# STM32WB55.net
KiCad netlist of a schematic drawn in Altium Designer
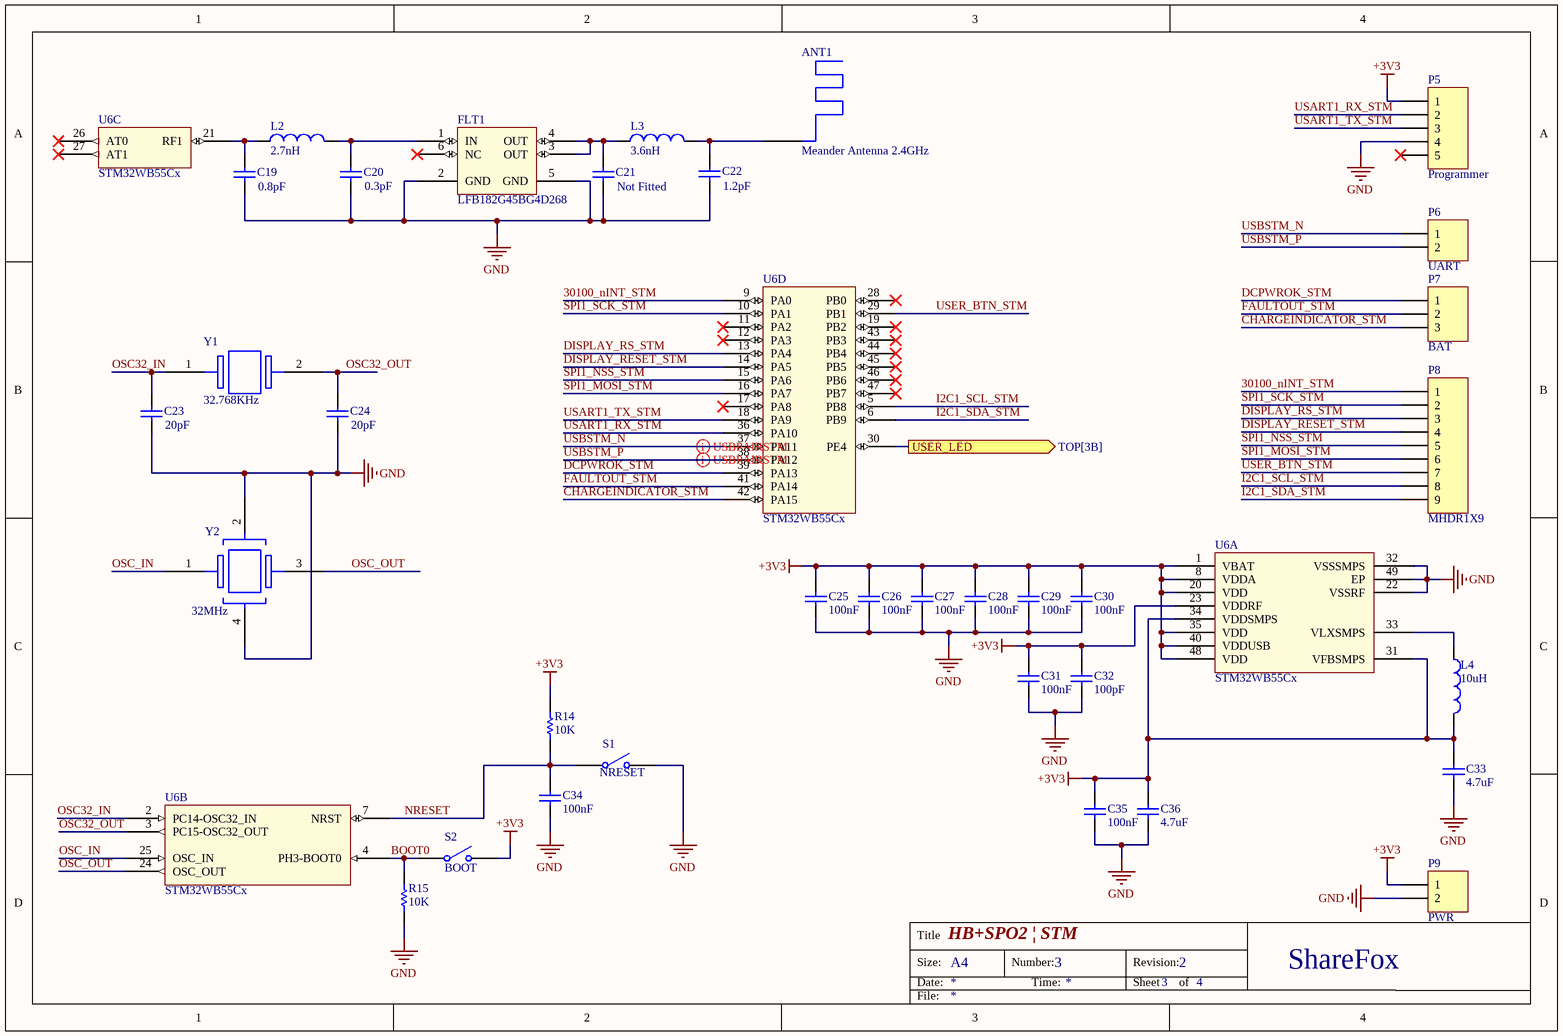
[diagram p0: STM32WB55.SchDoc]

(export (version "E")
  (design (tool "Eeschema 10.0.6"))
  (components
    (comp (ref "ANT1")
      (value "Meander Antenna 2.4GHz")
      (footprint "Meander2.4G")
      (description "PCB TRACE\r\nDONT TRY TO LOOK FOR PARTS")
      (libsource (lib "GenericContinued") (part "Meander Antenna 2.4GHz"))
    )
    (comp (ref "C19")
      (value "0.8pF")
      (footprint "C_0603")
      (description "Capacitor")
      (fields (field (name "PUBLISHER") "Altium Limited"))
      (libsource (lib "Miscellaneous Devices") (part "Cap"))
    )
    (comp (ref "C20")
      (value "0.3pF")
      (footprint "C_0603")
      (description "Capacitor")
      (fields (field (name "PUBLISHER") "Altium Limited"))
      (libsource (lib "Miscellaneous Devices") (part "Cap"))
    )
    (comp (ref "C21")
      (value "Not Fitted")
      (footprint "C_0603")
      (description "Capacitor")
      (fields (field (name "PUBLISHER") "Altium Limited"))
      (libsource (lib "Miscellaneous Devices") (part "Cap"))
    )
    (comp (ref "C22")
      (value "1.2pF")
      (footprint "C_0603")
      (description "Capacitor")
      (fields (field (name "PUBLISHER") "Altium Limited"))
      (libsource (lib "Miscellaneous Devices") (part "Cap"))
    )
    (comp (ref "C23")
      (value "20pF")
      (footprint "C_0603")
      (description "Capacitor")
      (fields (field (name "PUBLISHER") "Altium Limited"))
      (libsource (lib "Miscellaneous Devices") (part "Cap"))
    )
    (comp (ref "C24")
      (value "20pF")
      (footprint "C_0603")
      (description "Capacitor")
      (fields (field (name "PUBLISHER") "Altium Limited"))
      (libsource (lib "Miscellaneous Devices") (part "Cap"))
    )
    (comp (ref "C25")
      (value "100nF")
      (footprint "C_0603")
      (description "Capacitor")
      (fields (field (name "PUBLISHER") "Altium Limited"))
      (libsource (lib "Miscellaneous Devices") (part "Cap"))
    )
    (comp (ref "C26")
      (value "100nF")
      (footprint "C_0603")
      (description "Capacitor")
      (fields (field (name "PUBLISHER") "Altium Limited"))
      (libsource (lib "Miscellaneous Devices") (part "Cap"))
    )
    (comp (ref "C27")
      (value "100nF")
      (footprint "C_0603")
      (description "Capacitor")
      (fields (field (name "PUBLISHER") "Altium Limited"))
      (libsource (lib "Miscellaneous Devices") (part "Cap"))
    )
    (comp (ref "C28")
      (value "100nF")
      (footprint "C_0603")
      (description "Capacitor")
      (fields (field (name "PUBLISHER") "Altium Limited"))
      (libsource (lib "Miscellaneous Devices") (part "Cap"))
    )
    (comp (ref "C29")
      (value "100nF")
      (footprint "C_0603")
      (description "Capacitor")
      (fields (field (name "PUBLISHER") "Altium Limited"))
      (libsource (lib "Miscellaneous Devices") (part "Cap"))
    )
    (comp (ref "C30")
      (value "100nF")
      (footprint "C_0603")
      (description "Capacitor")
      (fields (field (name "PUBLISHER") "Altium Limited"))
      (libsource (lib "Miscellaneous Devices") (part "Cap"))
    )
    (comp (ref "C31")
      (value "100nF")
      (footprint "C_0603")
      (description "Capacitor")
      (fields (field (name "PUBLISHER") "Altium Limited"))
      (libsource (lib "Miscellaneous Devices") (part "Cap"))
    )
    (comp (ref "C32")
      (value "100pF")
      (footprint "C_0603")
      (description "Capacitor")
      (fields (field (name "PUBLISHER") "Altium Limited"))
      (libsource (lib "Miscellaneous Devices") (part "Cap"))
    )
    (comp (ref "C33")
      (value "4.7uF")
      (footprint "C_1206")
      (description "Capacitor")
      (fields (field (name "PUBLISHER") "Altium Limited"))
      (libsource (lib "Miscellaneous Devices") (part "Cap"))
    )
    (comp (ref "C34")
      (value "100nF")
      (footprint "C_0603")
      (description "Capacitor")
      (fields (field (name "PUBLISHER") "Altium Limited"))
      (libsource (lib "Miscellaneous Devices") (part "Cap"))
    )
    (comp (ref "C35")
      (value "100nF")
      (footprint "C_0603")
      (description "Capacitor")
      (fields (field (name "PUBLISHER") "Altium Limited"))
      (libsource (lib "Miscellaneous Devices") (part "Cap"))
    )
    (comp (ref "C36")
      (value "4.7uF")
      (footprint "C_1206")
      (description "Capacitor")
      (fields (field (name "PUBLISHER") "Altium Limited"))
      (libsource (lib "Miscellaneous Devices") (part "Cap"))
    )
    (comp (ref "FLT1")
      (value "LFB182G45BG4D268")
      (footprint "LFB182G45BG4D268")
      (description "Ultra-small, low-profiled, lightweight band-pass filters.")
      (libsource (lib "GenericContinued") (part "LFB182G45BG4D268"))
    )
    (comp (ref "L2")
      (value "2.7nH")
      (footprint "L-0603")
      (description "Inductor")
      (fields (field (name "PUBLISHER") "Altium Limited"))
      (libsource (lib "Miscellaneous Devices") (part "Inductor"))
    )
    (comp (ref "L3")
      (value "3.6nH")
      (footprint "L-0603")
      (description "Inductor")
      (fields (field (name "PUBLISHER") "Altium Limited"))
      (libsource (lib "Miscellaneous Devices") (part "Inductor"))
    )
    (comp (ref "L4")
      (value "10uH")
      (footprint "L-0603")
      (description "Inductor")
      (fields (field (name "PUBLISHER") "Altium Limited"))
      (libsource (lib "Miscellaneous Devices") (part "Inductor"))
    )
    (comp (ref "P5")
      (value "Programmer")
      (footprint "HDR1X5")
      (description "Header, 5-Pin")
      (fields (field (name "PUBLISHER") "Altium Limited"))
      (libsource (lib "Miscellaneous Connectors") (part "MHDR1X5"))
    )
    (comp (ref "P6")
      (value "UART")
      (footprint "MHDR1X2")
      (description "Header, 2-Pin")
      (fields (field (name "PUBLISHER") "Altium Limited"))
      (libsource (lib "Miscellaneous Connectors") (part "MHDR1X2"))
    )
    (comp (ref "P7")
      (value "BAT")
      (footprint "MHDR1X3")
      (description "Header, 3-Pin")
      (fields (field (name "PUBLISHER") "Altium Limited"))
      (libsource (lib "Miscellaneous Connectors") (part "MHDR1X3"))
    )
    (comp (ref "P8")
      (value "MHDR1X9")
      (footprint "MHDR1X9")
      (description "Header, 9-Pin")
      (fields (field (name "PUBLISHER") "Altium Limited"))
      (libsource (lib "Miscellaneous Connectors") (part "MHDR1X9"))
    )
    (comp (ref "P9")
      (value "PWR")
      (footprint "MHDR1X2")
      (description "Header, 2-Pin")
      (fields (field (name "PUBLISHER") "Altium Limited"))
      (libsource (lib "Miscellaneous Connectors") (part "MHDR1X2"))
    )
    (comp (ref "R14")
      (value "10K")
      (footprint "C_0603")
      (description "Resistor")
      (fields (field (name "PUBLISHER") "Altium Limited"))
      (libsource (lib "Miscellaneous Devices") (part "Res1"))
    )
    (comp (ref "R15")
      (value "10K")
      (footprint "C_0603")
      (description "Resistor")
      (fields (field (name "PUBLISHER") "Altium Limited"))
      (libsource (lib "Miscellaneous Devices") (part "Res1"))
    )
    (comp (ref "S1")
      (value "NRESET")
      (footprint "B3U-1000P-B")
      (description "Single-Pole, Single-Throw Switch")
      (fields (field (name "PUBLISHER") "Altium Limited"))
      (libsource (lib "Miscellaneous Devices") (part "SW-SPST"))
    )
    (comp (ref "S2")
      (value "BOOT")
      (footprint "B3U-1000P-B")
      (description "Single-Pole, Single-Throw Switch")
      (fields (field (name "PUBLISHER") "Altium Limited"))
      (libsource (lib "Miscellaneous Devices") (part "SW-SPST"))
    )
    (comp (ref "U6")
      (value "STM32WB55Cx")
      (footprint "QFN48P50S700x700EP560x560")
      (libsource (lib "ST") (part "STM32WB55Cx"))
    )
    (comp (ref "Y1")
      (value "32.768KHz")
      (footprint "ECX-31B")
      (libsource (lib "GenericContinued") (part "XTAL 3215"))
    )
    (comp (ref "Y2")
      (value "32MHz")
      (footprint "Y_3225")
      (libsource (lib "GenericContinued") (part "XTAL 3225 2_4GND"))
    )
  )
  (nets
    (net (code "1") (name "+3V3") (class "Default")
      (node (ref "C25") (pin "2") (pinfunction "2_2") (pintype "passive"))
      (node (ref "C26") (pin "2") (pinfunction "2_2") (pintype "passive"))
      (node (ref "C27") (pin "2") (pinfunction "2_2") (pintype "passive"))
      (node (ref "C28") (pin "2") (pinfunction "2_2") (pintype "passive"))
      (node (ref "C29") (pin "2") (pinfunction "2_2") (pintype "passive"))
      (node (ref "C30") (pin "2") (pinfunction "2_2") (pintype "passive"))
      (node (ref "C31") (pin "2") (pinfunction "2_2") (pintype "passive"))
      (node (ref "C32") (pin "2") (pinfunction "2_2") (pintype "passive"))
      (node (ref "C33") (pin "2") (pinfunction "2_2") (pintype "passive"))
      (node (ref "C35") (pin "2") (pinfunction "2_2") (pintype "passive"))
      (node (ref "C36") (pin "2") (pinfunction "2_2") (pintype "passive"))
      (node (ref "L4") (pin "2") (pinfunction "2_2") (pintype "passive"))
      (node (ref "P5") (pin "1") (pinfunction "1_1") (pintype "passive"))
      (node (ref "P9") (pin "1") (pinfunction "1_1") (pintype "passive"))
      (node (ref "R14") (pin "1") (pinfunction "1_1") (pintype "passive"))
      (node (ref "S2") (pin "2") (pinfunction "NO_2") (pintype "passive"))
      (node (ref "U6") (pin "1") (pinfunction "VBAT_1") (pintype "power_in"))
      (node (ref "U6") (pin "20") (pinfunction "VDD_20") (pintype "power_in"))
      (node (ref "U6") (pin "23") (pinfunction "VDDRF_23") (pintype "power_in"))
      (node (ref "U6") (pin "31") (pinfunction "VFBSMPS_31") (pintype "power_in"))
      (node (ref "U6") (pin "34") (pinfunction "VDDSMPS_34") (pintype "power_in"))
      (node (ref "U6") (pin "35") (pinfunction "VDD_35") (pintype "power_in"))
      (node (ref "U6") (pin "40") (pinfunction "VDDUSB_40") (pintype "power_in"))
      (node (ref "U6") (pin "48") (pinfunction "VDD_48") (pintype "power_in"))
      (node (ref "U6") (pin "8") (pinfunction "VDDA_8") (pintype "power_in"))
    )
    (net (code "2") (name "/30100_nINT_STM") (class "Default")
      (node (ref "P8") (pin "1") (pinfunction "1_1") (pintype "passive"))
      (node (ref "U6") (pin "9") (pinfunction "PA0_9") (pintype "bidirectional"))
    )
    (net (code "3") (name "/BOOT0") (class "Default")
      (node (ref "R15") (pin "2") (pinfunction "2_2") (pintype "passive"))
      (node (ref "S2") (pin "1") (pinfunction "COMMON_1") (pintype "passive"))
      (node (ref "U6") (pin "4") (pinfunction "PH3-BOOT0_4") (pintype "input"))
    )
    (net (code "4") (name "/CHARGEINDICATOR_STM") (class "Default")
      (node (ref "P7") (pin "3") (pinfunction "3_3") (pintype "passive"))
      (node (ref "U6") (pin "42") (pinfunction "PA15_42") (pintype "bidirectional"))
    )
    (net (code "5") (name "/DCPWROK_STM") (class "Default")
      (node (ref "P7") (pin "1") (pinfunction "1_1") (pintype "passive"))
      (node (ref "U6") (pin "39") (pinfunction "PA13_39") (pintype "bidirectional"))
    )
    (net (code "6") (name "/DISPLAY_RESET_STM") (class "Default")
      (node (ref "P8") (pin "4") (pinfunction "4_4") (pintype "passive"))
      (node (ref "U6") (pin "14") (pinfunction "PA5_14") (pintype "bidirectional"))
    )
    (net (code "7") (name "/DISPLAY_RS_STM") (class "Default")
      (node (ref "P8") (pin "3") (pinfunction "3_3") (pintype "passive"))
      (node (ref "U6") (pin "13") (pinfunction "PA4_13") (pintype "bidirectional"))
    )
    (net (code "8") (name "/FAULTOUT_STM") (class "Default")
      (node (ref "P7") (pin "2") (pinfunction "2_2") (pintype "passive"))
      (node (ref "U6") (pin "41") (pinfunction "PA14_41") (pintype "bidirectional"))
    )
    (net (code "9") (name "/I2C1_SCL_STM") (class "Default")
      (node (ref "P8") (pin "8") (pinfunction "8_8") (pintype "passive"))
      (node (ref "U6") (pin "5") (pinfunction "PB8_5") (pintype "bidirectional"))
    )
    (net (code "10") (name "/I2C1_SDA_STM") (class "Default")
      (node (ref "P8") (pin "9") (pinfunction "9_9") (pintype "passive"))
      (node (ref "U6") (pin "6") (pinfunction "PB9_6") (pintype "bidirectional"))
    )
    (net (code "11") (name "/NRESET") (class "Default")
      (node (ref "C34") (pin "1") (pinfunction "1_1") (pintype "passive"))
      (node (ref "R14") (pin "2") (pinfunction "2_2") (pintype "passive"))
      (node (ref "S1") (pin "1") (pinfunction "COMMON_1") (pintype "passive"))
      (node (ref "U6") (pin "7") (pinfunction "NRST_7") (pintype "bidirectional"))
    )
    (net (code "12") (name "/OSC32_IN") (class "Default")
      (node (ref "C23") (pin "2") (pinfunction "2_2") (pintype "passive"))
      (node (ref "U6") (pin "2") (pinfunction "PC14-OSC32_IN_2") (pintype "input"))
      (node (ref "Y1") (pin "1") (pinfunction "1_1") (pintype "passive"))
    )
    (net (code "13") (name "/OSC32_OUT") (class "Default")
      (node (ref "C24") (pin "2") (pinfunction "2_2") (pintype "passive"))
      (node (ref "U6") (pin "3") (pinfunction "PC15-OSC32_OUT_3") (pintype "output"))
      (node (ref "Y1") (pin "2") (pinfunction "2_2") (pintype "passive"))
    )
    (net (code "14") (name "/OSC_IN") (class "Default")
      (node (ref "U6") (pin "25") (pinfunction "OSC_IN_25") (pintype "input"))
      (node (ref "Y2") (pin "1") (pinfunction "1_1") (pintype "passive"))
    )
    (net (code "15") (name "/OSC_OUT") (class "Default")
      (node (ref "U6") (pin "24") (pinfunction "OSC_OUT_24") (pintype "output"))
      (node (ref "Y2") (pin "3") (pinfunction "3_3") (pintype "passive"))
    )
    (net (code "16") (name "/SPI1_MOSI_STM") (class "Default")
      (node (ref "P8") (pin "6") (pinfunction "6_6") (pintype "passive"))
      (node (ref "U6") (pin "16") (pinfunction "PA7_16") (pintype "bidirectional"))
    )
    (net (code "17") (name "/SPI1_NSS_STM") (class "Default")
      (node (ref "P8") (pin "5") (pinfunction "5_5") (pintype "passive"))
      (node (ref "U6") (pin "15") (pinfunction "PA6_15") (pintype "bidirectional"))
    )
    (net (code "18") (name "/SPI1_SCK_STM") (class "Default")
      (node (ref "P8") (pin "2") (pinfunction "2_2") (pintype "passive"))
      (node (ref "U6") (pin "10") (pinfunction "PA1_10") (pintype "bidirectional"))
    )
    (net (code "19") (name "/USART1_RX_STM") (class "Default")
      (node (ref "P5") (pin "2") (pinfunction "2_2") (pintype "passive"))
      (node (ref "U6") (pin "36") (pinfunction "PA10_36") (pintype "bidirectional"))
    )
    (net (code "20") (name "/USART1_TX_STM") (class "Default")
      (node (ref "P5") (pin "3") (pinfunction "3_3") (pintype "passive"))
      (node (ref "U6") (pin "18") (pinfunction "PA9_18") (pintype "bidirectional"))
    )
    (net (code "21") (name "/USBSTM_N") (class "Default")
      (node (ref "P6") (pin "1") (pinfunction "1_1") (pintype "passive"))
      (node (ref "U6") (pin "37") (pinfunction "PA11_37") (pintype "bidirectional"))
    )
    (net (code "22") (name "/USBSTM_P") (class "Default")
      (node (ref "P6") (pin "2") (pinfunction "2_2") (pintype "passive"))
      (node (ref "U6") (pin "38") (pinfunction "PA12_38") (pintype "bidirectional"))
    )
    (net (code "23") (name "/USER_BTN_STM") (class "Default")
      (node (ref "P8") (pin "7") (pinfunction "7_7") (pintype "passive"))
      (node (ref "U6") (pin "29") (pinfunction "PB1_29") (pintype "bidirectional"))
    )
    (net (code "24") (name "/USER_LED") (class "Default")
      (node (ref "U6") (pin "30") (pinfunction "PE4_30") (pintype "bidirectional"))
    )
    (net (code "25") (name "GND") (class "Default")
      (node (ref "C19") (pin "1") (pinfunction "1_1") (pintype "passive"))
      (node (ref "C20") (pin "1") (pinfunction "1_1") (pintype "passive"))
      (node (ref "C21") (pin "1") (pinfunction "1_1") (pintype "passive"))
      (node (ref "C22") (pin "1") (pinfunction "1_1") (pintype "passive"))
      (node (ref "C23") (pin "1") (pinfunction "1_1") (pintype "passive"))
      (node (ref "C24") (pin "1") (pinfunction "1_1") (pintype "passive"))
      (node (ref "C25") (pin "1") (pinfunction "1_1") (pintype "passive"))
      (node (ref "C26") (pin "1") (pinfunction "1_1") (pintype "passive"))
      (node (ref "C27") (pin "1") (pinfunction "1_1") (pintype "passive"))
      (node (ref "C28") (pin "1") (pinfunction "1_1") (pintype "passive"))
      (node (ref "C29") (pin "1") (pinfunction "1_1") (pintype "passive"))
      (node (ref "C30") (pin "1") (pinfunction "1_1") (pintype "passive"))
      (node (ref "C31") (pin "1") (pinfunction "1_1") (pintype "passive"))
      (node (ref "C32") (pin "1") (pinfunction "1_1") (pintype "passive"))
      (node (ref "C33") (pin "1") (pinfunction "1_1") (pintype "passive"))
      (node (ref "C34") (pin "2") (pinfunction "2_2") (pintype "passive"))
      (node (ref "C35") (pin "1") (pinfunction "1_1") (pintype "passive"))
      (node (ref "C36") (pin "1") (pinfunction "1_1") (pintype "passive"))
      (node (ref "FLT1") (pin "2") (pinfunction "GND_2") (pintype "power_in"))
      (node (ref "FLT1") (pin "5") (pinfunction "GND_5") (pintype "power_in"))
      (node (ref "P5") (pin "4") (pinfunction "4_4") (pintype "passive"))
      (node (ref "P9") (pin "2") (pinfunction "2_2") (pintype "passive"))
      (node (ref "R15") (pin "1") (pinfunction "1_1") (pintype "passive"))
      (node (ref "S1") (pin "2") (pinfunction "NO_2") (pintype "passive"))
      (node (ref "U6") (pin "22") (pinfunction "VSSRF_22") (pintype "power_in"))
      (node (ref "U6") (pin "32") (pinfunction "VSSSMPS_32") (pintype "power_in"))
      (node (ref "U6") (pin "49") (pinfunction "EP_49") (pintype "power_in"))
      (node (ref "Y2") (pin "2") (pinfunction "2_2") (pintype "passive"))
      (node (ref "Y2") (pin "4") (pinfunction "4_4") (pintype "passive"))
    )
    (net (code "26") (name "Net-(ANT1-Pad1)") (class "Default")
      (node (ref "ANT1") (pin "1") (pintype "passive"))
      (node (ref "C22") (pin "2") (pinfunction "2_2") (pintype "passive"))
      (node (ref "L3") (pin "2") (pinfunction "2_2") (pintype "passive"))
    )
    (net (code "27") (name "Net-(C21-Pad2)") (class "Default")
      (node (ref "C21") (pin "2") (pinfunction "2_2") (pintype "passive"))
      (node (ref "FLT1") (pin "3") (pinfunction "OUT_3") (pintype "bidirectional"))
      (node (ref "FLT1") (pin "4") (pinfunction "OUT_4") (pintype "bidirectional"))
      (node (ref "L3") (pin "1") (pinfunction "1_1") (pintype "passive"))
    )
    (net (code "28") (name "Net-(FLT1-IN)") (class "Default")
      (node (ref "C20") (pin "2") (pinfunction "2_2") (pintype "passive"))
      (node (ref "FLT1") (pin "1") (pinfunction "IN_1") (pintype "bidirectional"))
      (node (ref "L2") (pin "2") (pinfunction "2_2") (pintype "passive"))
    )
    (net (code "29") (name "Net-(U6A-VLXSMPS)") (class "Default")
      (node (ref "L4") (pin "1") (pinfunction "1_1") (pintype "passive"))
      (node (ref "U6") (pin "33") (pinfunction "VLXSMPS_33") (pintype "power_in"))
    )
    (net (code "30") (name "Net-(U6C-RF1)") (class "Default")
      (node (ref "C19") (pin "2") (pinfunction "2_2") (pintype "passive"))
      (node (ref "L2") (pin "1") (pinfunction "1_1") (pintype "passive"))
      (node (ref "U6") (pin "21") (pinfunction "RF1_21") (pintype "bidirectional"))
    )
    (net (code "31") (name "unconnected-(FLT1-NC-Pad6)") (class "Default")
      (node (ref "FLT1") (pin "6") (pinfunction "NC_6") (pintype "bidirectional+no_connect"))
    )
    (net (code "32") (name "unconnected-(P5-Pad5)") (class "Default")
      (node (ref "P5") (pin "5") (pinfunction "5_5") (pintype "passive+no_connect"))
    )
    (net (code "33") (name "unconnected-(U6C-AT0-Pad26)") (class "Default")
      (node (ref "U6") (pin "26") (pinfunction "AT0_26") (pintype "output+no_connect"))
    )
    (net (code "34") (name "unconnected-(U6C-AT1-Pad27)") (class "Default")
      (node (ref "U6") (pin "27") (pinfunction "AT1_27") (pintype "output+no_connect"))
    )
    (net (code "35") (name "unconnected-(U6D-PA2-Pad11)") (class "Default")
      (node (ref "U6") (pin "11") (pinfunction "PA2_11") (pintype "bidirectional+no_connect"))
    )
    (net (code "36") (name "unconnected-(U6D-PA3-Pad12)") (class "Default")
      (node (ref "U6") (pin "12") (pinfunction "PA3_12") (pintype "bidirectional+no_connect"))
    )
    (net (code "37") (name "unconnected-(U6D-PA8-Pad17)") (class "Default")
      (node (ref "U6") (pin "17") (pinfunction "PA8_17") (pintype "bidirectional+no_connect"))
    )
    (net (code "38") (name "unconnected-(U6D-PB0-Pad28)") (class "Default")
      (node (ref "U6") (pin "28") (pinfunction "PB0_28") (pintype "bidirectional+no_connect"))
    )
    (net (code "39") (name "unconnected-(U6D-PB2-Pad19)") (class "Default")
      (node (ref "U6") (pin "19") (pinfunction "PB2_19") (pintype "bidirectional+no_connect"))
    )
    (net (code "40") (name "unconnected-(U6D-PB3-Pad43)") (class "Default")
      (node (ref "U6") (pin "43") (pinfunction "PB3_43") (pintype "bidirectional+no_connect"))
    )
    (net (code "41") (name "unconnected-(U6D-PB4-Pad44)") (class "Default")
      (node (ref "U6") (pin "44") (pinfunction "PB4_44") (pintype "bidirectional+no_connect"))
    )
    (net (code "42") (name "unconnected-(U6D-PB5-Pad45)") (class "Default")
      (node (ref "U6") (pin "45") (pinfunction "PB5_45") (pintype "bidirectional+no_connect"))
    )
    (net (code "43") (name "unconnected-(U6D-PB6-Pad46)") (class "Default")
      (node (ref "U6") (pin "46") (pinfunction "PB6_46") (pintype "bidirectional+no_connect"))
    )
    (net (code "44") (name "unconnected-(U6D-PB7-Pad47)") (class "Default")
      (node (ref "U6") (pin "47") (pinfunction "PB7_47") (pintype "bidirectional+no_connect"))
    )
  )
)
